# HCSR04_RingSection_C.net
KiCad netlist of a schematic drawn in EAGLE
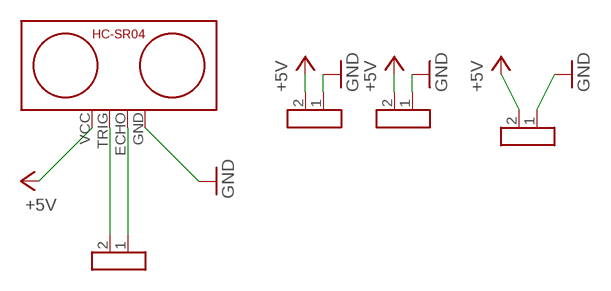
[diagram p0: schematic, sheet 1]

(export (version "E")
  (design (tool "Eeschema 10.0.6"))
  (components
    (comp (ref "U$1")
      (value "HCSR04")
      (footprint "eagle-import:HCSR04")
      (libsource (lib "eagle-import") (part "HCSR04"))
    )
    (comp (ref "U$2")
      (value "2XHEADER")
      (footprint "eagle-import:2XHEADER")
      (libsource (lib "eagle-import") (part "2XHEADER"))
    )
    (comp (ref "U$3")
      (value "2XHEADER")
      (footprint "eagle-import:2XHEADER")
      (libsource (lib "eagle-import") (part "2XHEADER"))
    )
    (comp (ref "U$4")
      (value "2XHEADER")
      (footprint "eagle-import:2XHEADER")
      (libsource (lib "eagle-import") (part "2XHEADER"))
    )
    (comp (ref "U$6")
      (value "2XHEADER")
      (footprint "eagle-import:2XHEADER")
      (libsource (lib "eagle-import") (part "2XHEADER"))
    )
  )
  (nets
    (net (code "1") (name "+5V") (class "Default")
      (node (ref "U$1") (pin "VCC") (pinfunction "VCC_VCC") (pintype "passive"))
      (node (ref "U$2") (pin "2") (pinfunction "2_2") (pintype "passive"))
      (node (ref "U$3") (pin "2") (pinfunction "2_2") (pintype "passive"))
      (node (ref "U$6") (pin "2") (pinfunction "2_2") (pintype "passive"))
    )
    (net (code "2") (name "GND") (class "Default")
      (node (ref "U$1") (pin "GND") (pinfunction "GND_GND") (pintype "passive"))
      (node (ref "U$2") (pin "1") (pinfunction "1_1") (pintype "passive"))
      (node (ref "U$3") (pin "1") (pinfunction "1_1") (pintype "passive"))
      (node (ref "U$6") (pin "1") (pinfunction "1_1") (pintype "passive"))
    )
    (net (code "3") (name "Net-(U$1-PadECHO)") (class "Default")
      (node (ref "U$1") (pin "ECHO") (pinfunction "ECHO_ECHO") (pintype "passive"))
      (node (ref "U$4") (pin "1") (pinfunction "1_1") (pintype "passive"))
    )
    (net (code "4") (name "Net-(U$1-PadTRIG)") (class "Default")
      (node (ref "U$1") (pin "TRIG") (pinfunction "TRIG_TRIG") (pintype "passive"))
      (node (ref "U$4") (pin "2") (pinfunction "2_2") (pintype "passive"))
    )
  )
)
